# EverythingBoard.net
KiCad netlist of a schematic drawn in EasyEDA Pro
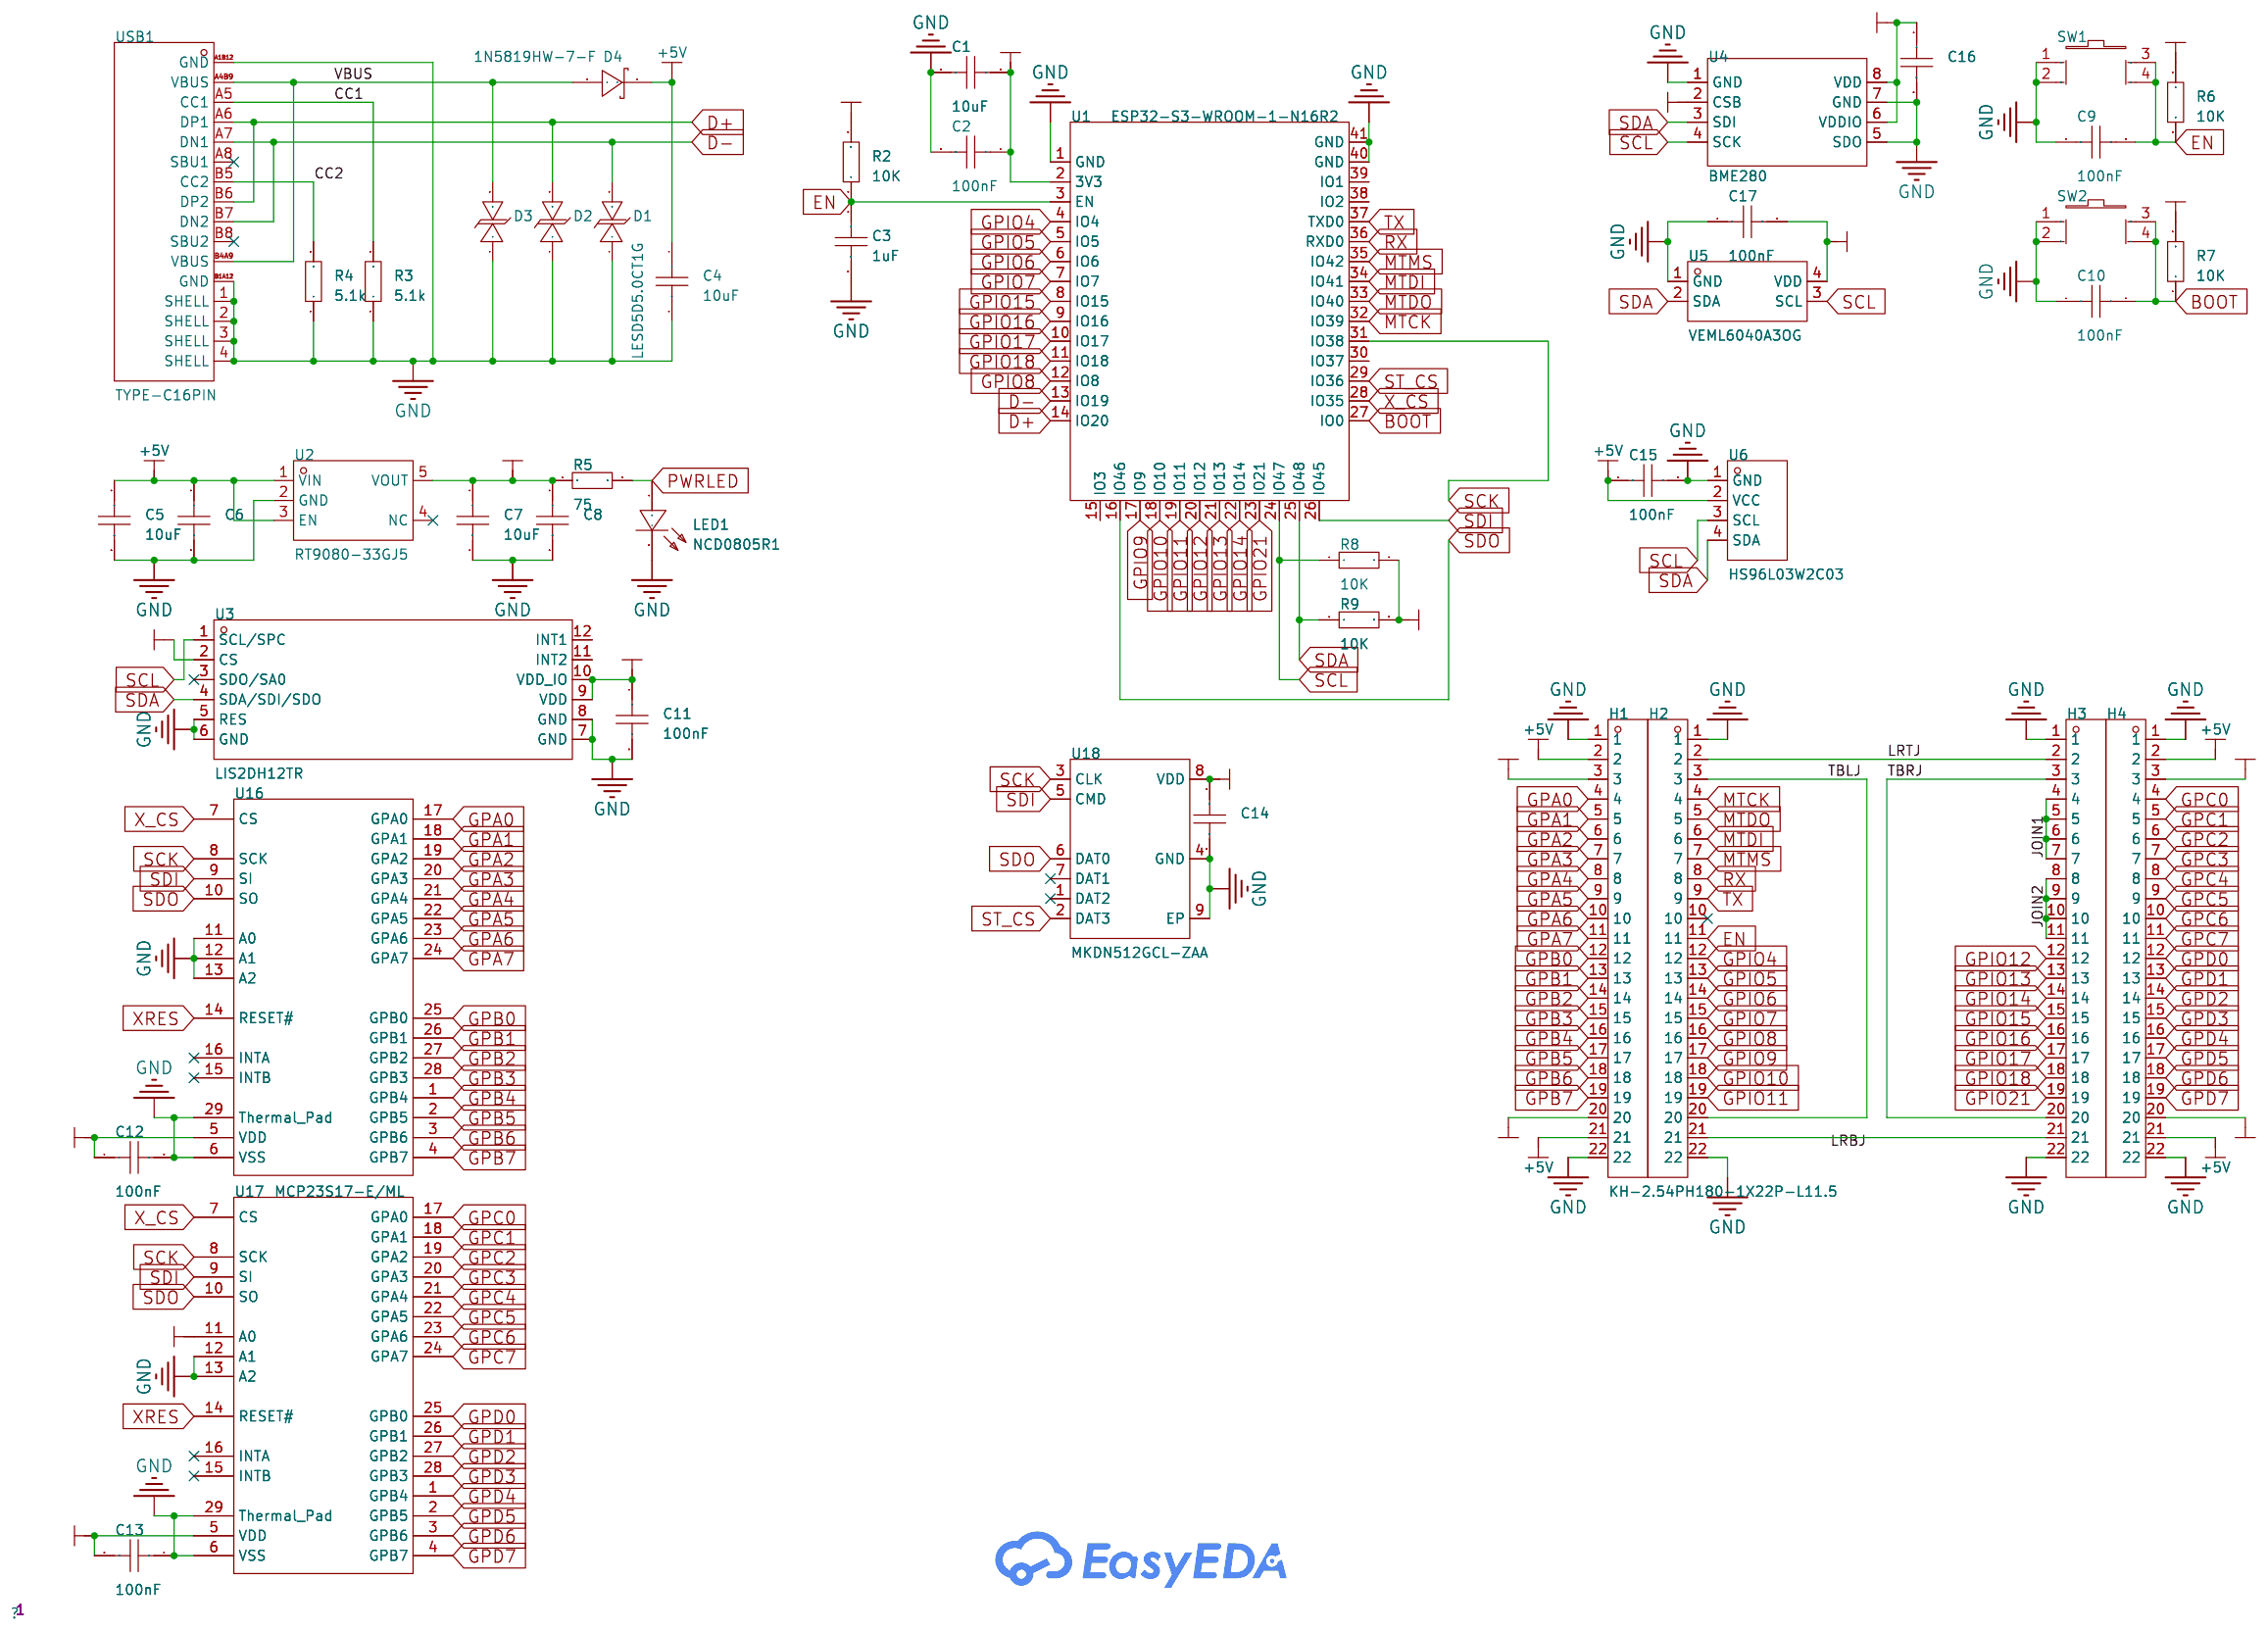
[diagram p0: schematic sheet]

(export (version "E")
  (design (tool "Eeschema 10.0.6"))
  (components
    (comp (ref "C1")
      (value "10uF")
      (footprint "easyedapro:C0603")
      (libsource (lib "easyedapro") (part "CAP"))
    )
    (comp (ref "C2")
      (value "100nF")
      (footprint "easyedapro:C0603")
      (libsource (lib "easyedapro") (part "CAP"))
    )
    (comp (ref "C3") (value "1uF") (footprint "easyedapro:C0603") (libsource (lib "easyedapro") (part "CAP")))
    (comp (ref "C4")
      (value "10uF")
      (footprint "easyedapro:C0603")
      (libsource (lib "easyedapro") (part "CAP"))
    )
    (comp (ref "C5")
      (value "10uF")
      (footprint "easyedapro:C0603")
      (libsource (lib "easyedapro") (part "CAP"))
    )
    (comp (ref "C6")
      (value "100nF")
      (footprint "easyedapro:C0603")
      (libsource (lib "easyedapro") (part "CAP"))
    )
    (comp (ref "C7")
      (value "10uF")
      (footprint "easyedapro:C0603")
      (libsource (lib "easyedapro") (part "CAP"))
    )
    (comp (ref "C8")
      (value "100nF")
      (footprint "easyedapro:C0603")
      (libsource (lib "easyedapro") (part "CAP"))
    )
    (comp (ref "C9")
      (value "100nF")
      (footprint "easyedapro:C0603")
      (libsource (lib "easyedapro") (part "CAP"))
    )
    (comp (ref "C10")
      (value "100nF")
      (footprint "easyedapro:C0603")
      (libsource (lib "easyedapro") (part "CAP"))
    )
    (comp (ref "C11")
      (value "100nF")
      (footprint "easyedapro:C0603")
      (libsource (lib "easyedapro") (part "CAP"))
    )
    (comp (ref "C12")
      (value "100nF")
      (footprint "easyedapro:C0603")
      (libsource (lib "easyedapro") (part "CAP"))
    )
    (comp (ref "C13")
      (value "100nF")
      (footprint "easyedapro:C0603")
      (libsource (lib "easyedapro") (part "CAP"))
    )
    (comp (ref "C14")
      (value "100nF")
      (footprint "easyedapro:C0603")
      (libsource (lib "easyedapro") (part "CAP"))
    )
    (comp (ref "C15")
      (value "100nF")
      (footprint "easyedapro:C0603")
      (libsource (lib "easyedapro") (part "CAP"))
    )
    (comp (ref "C16")
      (value "100nF")
      (footprint "easyedapro:C0603")
      (libsource (lib "easyedapro") (part "CAP"))
    )
    (comp (ref "C17")
      (value "100nF")
      (footprint "easyedapro:C0603")
      (libsource (lib "easyedapro") (part "CAP"))
    )
    (comp (ref "D1")
      (value "LESD5D5.0CT1G")
      (footprint "easyedapro:SOD-523_L1.2-W0.8-LS1.6-BI")
      (fields (field (name "Manufacturer") "UMW(友台半导体)"))
      (libsource (lib "easyedapro") (part "LESD5D5.0CT1G_C5199850"))
    )
    (comp (ref "D2")
      (value "LESD5D5.0CT1G")
      (footprint "easyedapro:SOD-523_L1.2-W0.8-LS1.6-BI")
      (fields (field (name "Manufacturer") "UMW(友台半导体)"))
      (libsource (lib "easyedapro") (part "LESD5D5.0CT1G_C5199850"))
    )
    (comp (ref "D3")
      (value "LESD5D5.0CT1G")
      (footprint "easyedapro:SOD-523_L1.2-W0.8-LS1.6-BI")
      (fields (field (name "Manufacturer") "UMW(友台半导体)"))
      (libsource (lib "easyedapro") (part "LESD5D5.0CT1G_C5199850"))
    )
    (comp (ref "D4")
      (value "1N5819HW-7-F")
      (footprint "easyedapro:SOD-123_L2.7-W1.6-LS3.7-RD")
      (fields (field (name "Manufacturer") "DIODES(美台)"))
      (libsource (lib "easyedapro") (part "1N5819HW-7-F"))
    )
    (comp (ref "H1")
      (value "KH-2.54PH180-1X22P-L11.5")
      (footprint "easyedapro:HDR-TH_22P-P2.54-V-M")
      (description "Pin Structure:1x22P Pitch:2.54mm Number of Rows:Single Row")
      (fields (field (name "Manufacturer") "kinghelm(金航标)"))
      (libsource (lib "easyedapro") (part "KH-2.54PH180-1X22P-L11.5"))
    )
    (comp (ref "H2")
      (value "KH-2.54PH180-1X22P-L11.5")
      (footprint "easyedapro:HDR-TH_22P-P2.54-V-M")
      (description "Pin Structure:1x22P Pitch:2.54mm Number of Rows:Single Row")
      (fields (field (name "Manufacturer") "kinghelm(金航标)"))
      (libsource (lib "easyedapro") (part "KH-2.54PH180-1X22P-L11.5"))
    )
    (comp (ref "H3")
      (value "KH-2.54PH180-1X22P-L11.5")
      (footprint "easyedapro:HDR-TH_22P-P2.54-V-M")
      (description "Pin Structure:1x22P Pitch:2.54mm Number of Rows:Single Row")
      (fields (field (name "Manufacturer") "kinghelm(金航标)"))
      (libsource (lib "easyedapro") (part "KH-2.54PH180-1X22P-L11.5"))
    )
    (comp (ref "H4")
      (value "KH-2.54PH180-1X22P-L11.5")
      (footprint "easyedapro:HDR-TH_22P-P2.54-V-M")
      (description "Pin Structure:1x22P Pitch:2.54mm Number of Rows:Single Row")
      (fields (field (name "Manufacturer") "kinghelm(金航标)"))
      (libsource (lib "easyedapro") (part "KH-2.54PH180-1X22P-L11.5"))
    )
    (comp (ref "LED1")
      (value "NCD0805R1")
      (footprint "easyedapro:LED0805-R-RD")
      (fields (field (name "Manufacturer") "国星光电"))
      (libsource (lib "easyedapro") (part "FC-2012HRK-620D"))
    )
    (comp (ref "R2") (value "10K") (footprint "easyedapro:R0603") (libsource (lib "easyedapro") (part "Res")))
    (comp (ref "R3")
      (value "5.1k")
      (footprint "easyedapro:R0603")
      (libsource (lib "easyedapro") (part "Res"))
    )
    (comp (ref "R4")
      (value "5.1k")
      (footprint "easyedapro:R0603")
      (libsource (lib "easyedapro") (part "Res"))
    )
    (comp (ref "R5") (value "75") (footprint "easyedapro:R0603") (libsource (lib "easyedapro") (part "Res")))
    (comp (ref "R6") (value "10K") (footprint "easyedapro:R0603") (libsource (lib "easyedapro") (part "Res")))
    (comp (ref "R7") (value "10K") (footprint "easyedapro:R0603") (libsource (lib "easyedapro") (part "Res")))
    (comp (ref "R8") (value "10K") (footprint "easyedapro:R0603") (libsource (lib "easyedapro") (part "Res")))
    (comp (ref "R9") (value "10K") (footprint "easyedapro:R0603") (libsource (lib "easyedapro") (part "Res")))
    (comp (ref "SW1")
      (value "PTS810SJG250SMTRLFS")
      (footprint "easyedapro:SW-SMD_4P_PTS810SJM250SMTRLFS")
      (fields (field (name "Manufacturer") "C&K"))
      (libsource (lib "easyedapro") (part "PTS810SJG250SMTRLFS"))
    )
    (comp (ref "SW2")
      (value "PTS810SJG250SMTRLFS")
      (footprint "easyedapro:SW-SMD_4P_PTS810SJM250SMTRLFS")
      (fields (field (name "Manufacturer") "C&K"))
      (libsource (lib "easyedapro") (part "PTS810SJG250SMTRLFS"))
    )
    (comp (ref "U1")
      (value "ESP32-S3-WROOM-1-N16R2")
      (footprint "easyedapro:WIRELM-SMD_ESP32-S3-WROOM-1")
      (fields (field (name "Manufacturer") "ESPRESSIF(乐鑫)"))
      (libsource (lib "easyedapro") (part "ESP32-S3-WROOM-1(N16R2)"))
    )
    (comp (ref "U2")
      (value "RT9080-33GJ5")
      (footprint "easyedapro:TSOT-23-5_L2.9-W1.6-P0.95-LS2.8-BL")
      (description "+3V3")
      (fields (field (name "Manufacturer") "RICHTEK(立锜)"))
      (libsource (lib "easyedapro") (part "RT9080-33GJ5"))
    )
    (comp (ref "U3")
      (value "LIS2DH12TR")
      (footprint "easyedapro:LGA-12_L2.0-W2.0-P0.50-BL")
      (fields (field (name "Manufacturer") "ST(意法半导体)"))
      (libsource (lib "easyedapro") (part "LIS2DH12TR"))
    )
    (comp (ref "U4")
      (value "BME280")
      (footprint "easyedapro:LGA-8_BME280_BL")
      (description "Voltage - Supply:1.71V~3.6V Voltage - Supply:1.71V~3.6V")
      (fields (field (name "Manufacturer") "Bosch(博世)"))
      (libsource (lib "easyedapro") (part "BME280"))
    )
    (comp (ref "U5")
      (value "VEML6040A3OG")
      (footprint "easyedapro:SENSOR_SMD_VEML6040A3OG")
      (fields (field (name "Manufacturer") "VISHAY(威世)"))
      (libsource (lib "easyedapro") (part "VEML6040A3OG"))
    )
    (comp (ref "U6")
      (value "HS96L03W2C03")
      (footprint "easyedapro:OLED-TH_L27.8-W27.2-P2.54_C9900033791")
      (fields (field (name "Manufacturer") "HS(汉昇)"))
      (libsource (lib "easyedapro") (part "HS96L03W2C03"))
    )
    (comp (ref "U16")
      (value "MCP23S17-E/ML")
      (footprint "easyedapro:QFN-28_L6.0-W6.0-P0.65-BL-EP")
      (fields (field (name "Manufacturer") "MICROCHIP(美国微芯)"))
      (libsource (lib "easyedapro") (part "MCP23S17-E/ML"))
    )
    (comp (ref "U17")
      (value "MCP23S17-E/ML")
      (footprint "easyedapro:QFN-28_L6.0-W6.0-P0.65-BL-EP")
      (fields (field (name "Manufacturer") "MICROCHIP(美国微芯)"))
      (libsource (lib "easyedapro") (part "MCP23S17-E/ML"))
    )
    (comp (ref "U18")
      (value "MKDN512GCL-ZAA")
      (footprint "easyedapro:LGA-16_L12.5-W9.0-P1.27-TL-EP")
      (fields (field (name "Manufacturer") "MK(米客方德)"))
      (libsource (lib "easyedapro") (part "MKDN512GCL-ZAA"))
    )
    (comp (ref "USB1")
      (value "TYPE-C16PIN")
      (footprint "easyedapro:USB-C-SMD_TYPE-C16PIN")
      (fields (field (name "Manufacturer") "SHOU HAN(首韩)"))
      (libsource (lib "easyedapro") (part "TYPE-C16PIN"))
    )
  )
  (nets
    (net (code "1") (name "+3V3") (class "Default")
      (node (ref "C1") (pin "1") (pinfunction "1_1") (pintype "input"))
      (node (ref "C11") (pin "1") (pinfunction "1_1") (pintype "input"))
      (node (ref "C12") (pin "1") (pinfunction "1_1") (pintype "input"))
      (node (ref "C13") (pin "2") (pinfunction "2_2") (pintype "input"))
      (node (ref "C14") (pin "1") (pinfunction "1_1") (pintype "input"))
      (node (ref "C16") (pin "1") (pinfunction "1_1") (pintype "input"))
      (node (ref "C17") (pin "2") (pinfunction "2_2") (pintype "input"))
      (node (ref "C2") (pin "1") (pinfunction "1_1") (pintype "input"))
      (node (ref "C7") (pin "1") (pinfunction "1_1") (pintype "input"))
      (node (ref "C8") (pin "1") (pinfunction "1_1") (pintype "input"))
      (node (ref "H1") (pin "20") (pinfunction "20_20") (pintype "unspecified"))
      (node (ref "H1") (pin "3") (pinfunction "3_3") (pintype "unspecified"))
      (node (ref "H4") (pin "20") (pinfunction "20_20") (pintype "unspecified"))
      (node (ref "H4") (pin "3") (pinfunction "3_3") (pintype "unspecified"))
      (node (ref "R2") (pin "2") (pinfunction "2_2") (pintype "input"))
      (node (ref "R5") (pin "1") (pinfunction "1_1") (pintype "input"))
      (node (ref "R6") (pin "1") (pinfunction "1_1") (pintype "input"))
      (node (ref "R7") (pin "2") (pinfunction "2_2") (pintype "input"))
      (node (ref "R8") (pin "2") (pinfunction "2_2") (pintype "input"))
      (node (ref "R9") (pin "2") (pinfunction "2_2") (pintype "input"))
      (node (ref "U1") (pin "2") (pinfunction "3V3_2") (pintype "unspecified"))
      (node (ref "U16") (pin "5") (pinfunction "VDD_5") (pintype "input"))
      (node (ref "U17") (pin "11") (pinfunction "A0_11") (pintype "input"))
      (node (ref "U17") (pin "5") (pinfunction "VDD_5") (pintype "input"))
      (node (ref "U18") (pin "8") (pinfunction "VDD_8") (pintype "unspecified"))
      (node (ref "U2") (pin "5") (pinfunction "VOUT_5") (pintype "unspecified"))
      (node (ref "U3") (pin "10") (pinfunction "VDD_IO_10") (pintype "unspecified"))
      (node (ref "U3") (pin "2") (pinfunction "CS_2") (pintype "unspecified"))
      (node (ref "U3") (pin "9") (pinfunction "VDD_9") (pintype "unspecified"))
      (node (ref "U4") (pin "2") (pinfunction "CSB_2") (pintype "unspecified"))
      (node (ref "U4") (pin "6") (pinfunction "VDDIO_6") (pintype "unspecified"))
      (node (ref "U4") (pin "8") (pinfunction "VDD_8") (pintype "unspecified"))
      (node (ref "U5") (pin "4") (pinfunction "VDD_4") (pintype "unspecified"))
    )
    (net (code "2") (name "+5V") (class "Default")
      (node (ref "C15") (pin "1") (pinfunction "1_1") (pintype "input"))
      (node (ref "C4") (pin "1") (pinfunction "1_1") (pintype "input"))
      (node (ref "C5") (pin "1") (pinfunction "1_1") (pintype "input"))
      (node (ref "C6") (pin "1") (pinfunction "1_1") (pintype "input"))
      (node (ref "D4") (pin "1") (pinfunction "K_1") (pintype "unspecified"))
      (node (ref "H1") (pin "2") (pinfunction "2_2") (pintype "unspecified"))
      (node (ref "H1") (pin "21") (pinfunction "21_21") (pintype "unspecified"))
      (node (ref "H4") (pin "2") (pinfunction "2_2") (pintype "unspecified"))
      (node (ref "H4") (pin "21") (pinfunction "21_21") (pintype "unspecified"))
      (node (ref "U2") (pin "1") (pinfunction "VIN_1") (pintype "unspecified"))
      (node (ref "U2") (pin "3") (pinfunction "EN_3") (pintype "unspecified"))
      (node (ref "U6") (pin "2") (pinfunction "VCC_2") (pintype "unspecified"))
    )
    (net (code "3") (name "/CC1") (class "Default")
      (node (ref "R3") (pin "2") (pinfunction "2_2") (pintype "input"))
      (node (ref "USB1") (pin "A5") (pinfunction "CC1_A5") (pintype "unspecified"))
    )
    (net (code "4") (name "/CC2") (class "Default")
      (node (ref "R4") (pin "2") (pinfunction "2_2") (pintype "input"))
      (node (ref "USB1") (pin "B5") (pinfunction "CC2_B5") (pintype "unspecified"))
    )
    (net (code "5") (name "/JOIN1") (class "Default")
      (node (ref "H3") (pin "4") (pinfunction "4_4") (pintype "unspecified"))
      (node (ref "H3") (pin "5") (pinfunction "5_5") (pintype "unspecified"))
      (node (ref "H3") (pin "6") (pinfunction "6_6") (pintype "unspecified"))
      (node (ref "H3") (pin "7") (pinfunction "7_7") (pintype "unspecified"))
    )
    (net (code "6") (name "/JOIN2") (class "Default")
      (node (ref "H3") (pin "10") (pinfunction "10_10") (pintype "unspecified"))
      (node (ref "H3") (pin "11") (pinfunction "11_11") (pintype "unspecified"))
      (node (ref "H3") (pin "8") (pinfunction "8_8") (pintype "unspecified"))
      (node (ref "H3") (pin "9") (pinfunction "9_9") (pintype "unspecified"))
    )
    (net (code "7") (name "/LRBJ") (class "Default")
      (node (ref "H2") (pin "21") (pinfunction "21_21") (pintype "unspecified"))
      (node (ref "H3") (pin "21") (pinfunction "21_21") (pintype "unspecified"))
    )
    (net (code "8") (name "/LRTJ") (class "Default")
      (node (ref "H2") (pin "2") (pinfunction "2_2") (pintype "unspecified"))
      (node (ref "H3") (pin "2") (pinfunction "2_2") (pintype "unspecified"))
    )
    (net (code "9") (name "/TBLJ") (class "Default")
      (node (ref "H2") (pin "20") (pinfunction "20_20") (pintype "unspecified"))
      (node (ref "H2") (pin "3") (pinfunction "3_3") (pintype "unspecified"))
    )
    (net (code "10") (name "/TBRJ") (class "Default")
      (node (ref "H3") (pin "20") (pinfunction "20_20") (pintype "unspecified"))
      (node (ref "H3") (pin "3") (pinfunction "3_3") (pintype "unspecified"))
    )
    (net (code "11") (name "/VBUS") (class "Default")
      (node (ref "D3") (pin "2") (pinfunction "2_2") (pintype "unspecified"))
      (node (ref "D4") (pin "2") (pinfunction "A_2") (pintype "unspecified"))
      (node (ref "USB1") (pin "A4B9") (pinfunction "VBUS_A4B9") (pintype "unspecified"))
      (node (ref "USB1") (pin "B4A9") (pinfunction "VBUS_B4A9") (pintype "unspecified"))
    )
    (net (code "12") (name "BOOT") (class "Default")
      (node (ref "C10") (pin "2") (pinfunction "2_2") (pintype "input"))
      (node (ref "R7") (pin "1") (pinfunction "1_1") (pintype "input"))
      (node (ref "SW2") (pin "3") (pinfunction "3_3") (pintype "input"))
      (node (ref "SW2") (pin "4") (pinfunction "4_4") (pintype "input"))
      (node (ref "U1") (pin "27") (pinfunction "IO0_27") (pintype "unspecified"))
    )
    (net (code "13") (name "D+") (class "Default")
      (node (ref "D2") (pin "2") (pinfunction "2_2") (pintype "unspecified"))
      (node (ref "U1") (pin "14") (pinfunction "IO20_14") (pintype "unspecified"))
      (node (ref "USB1") (pin "A6") (pinfunction "DP1_A6") (pintype "unspecified"))
      (node (ref "USB1") (pin "B6") (pinfunction "DP2_B6") (pintype "unspecified"))
    )
    (net (code "14") (name "D-") (class "Default")
      (node (ref "D1") (pin "2") (pinfunction "2_2") (pintype "unspecified"))
      (node (ref "U1") (pin "13") (pinfunction "IO19_13") (pintype "unspecified"))
      (node (ref "USB1") (pin "A7") (pinfunction "DN1_A7") (pintype "unspecified"))
      (node (ref "USB1") (pin "B7") (pinfunction "DN2_B7") (pintype "unspecified"))
    )
    (net (code "15") (name "EN") (class "Default")
      (node (ref "C3") (pin "1") (pinfunction "1_1") (pintype "input"))
      (node (ref "C9") (pin "2") (pinfunction "2_2") (pintype "input"))
      (node (ref "H2") (pin "11") (pinfunction "11_11") (pintype "unspecified"))
      (node (ref "R2") (pin "1") (pinfunction "1_1") (pintype "input"))
      (node (ref "R6") (pin "2") (pinfunction "2_2") (pintype "input"))
      (node (ref "SW1") (pin "3") (pinfunction "3_3") (pintype "input"))
      (node (ref "SW1") (pin "4") (pinfunction "4_4") (pintype "input"))
      (node (ref "U1") (pin "3") (pinfunction "EN_3") (pintype "unspecified"))
    )
    (net (code "16") (name "GND") (class "Default")
      (node (ref "C1") (pin "2") (pinfunction "2_2") (pintype "input"))
      (node (ref "C10") (pin "1") (pinfunction "1_1") (pintype "input"))
      (node (ref "C11") (pin "2") (pinfunction "2_2") (pintype "input"))
      (node (ref "C12") (pin "2") (pinfunction "2_2") (pintype "input"))
      (node (ref "C13") (pin "1") (pinfunction "1_1") (pintype "input"))
      (node (ref "C14") (pin "2") (pinfunction "2_2") (pintype "input"))
      (node (ref "C15") (pin "2") (pinfunction "2_2") (pintype "input"))
      (node (ref "C16") (pin "2") (pinfunction "2_2") (pintype "input"))
      (node (ref "C17") (pin "1") (pinfunction "1_1") (pintype "input"))
      (node (ref "C2") (pin "2") (pinfunction "2_2") (pintype "input"))
      (node (ref "C3") (pin "2") (pinfunction "2_2") (pintype "input"))
      (node (ref "C4") (pin "2") (pinfunction "2_2") (pintype "input"))
      (node (ref "C5") (pin "2") (pinfunction "2_2") (pintype "input"))
      (node (ref "C6") (pin "2") (pinfunction "2_2") (pintype "input"))
      (node (ref "C7") (pin "2") (pinfunction "2_2") (pintype "input"))
      (node (ref "C8") (pin "2") (pinfunction "2_2") (pintype "input"))
      (node (ref "C9") (pin "1") (pinfunction "1_1") (pintype "input"))
      (node (ref "D1") (pin "1") (pinfunction "1_1") (pintype "unspecified"))
      (node (ref "D2") (pin "1") (pinfunction "1_1") (pintype "unspecified"))
      (node (ref "D3") (pin "1") (pinfunction "1_1") (pintype "unspecified"))
      (node (ref "H1") (pin "1") (pinfunction "1_1") (pintype "unspecified"))
      (node (ref "H1") (pin "22") (pinfunction "22_22") (pintype "unspecified"))
      (node (ref "H2") (pin "1") (pinfunction "1_1") (pintype "unspecified"))
      (node (ref "H2") (pin "22") (pinfunction "22_22") (pintype "unspecified"))
      (node (ref "H3") (pin "1") (pinfunction "1_1") (pintype "unspecified"))
      (node (ref "H3") (pin "22") (pinfunction "22_22") (pintype "unspecified"))
      (node (ref "H4") (pin "1") (pinfunction "1_1") (pintype "unspecified"))
      (node (ref "H4") (pin "22") (pinfunction "22_22") (pintype "unspecified"))
      (node (ref "LED1") (pin "2") (pinfunction "-_2") (pintype "unspecified"))
      (node (ref "R3") (pin "1") (pinfunction "1_1") (pintype "input"))
      (node (ref "R4") (pin "1") (pinfunction "1_1") (pintype "input"))
      (node (ref "SW1") (pin "1") (pinfunction "1_1") (pintype "input"))
      (node (ref "SW1") (pin "2") (pinfunction "2_2") (pintype "input"))
      (node (ref "SW2") (pin "1") (pinfunction "1_1") (pintype "input"))
      (node (ref "SW2") (pin "2") (pinfunction "2_2") (pintype "input"))
      (node (ref "U1") (pin "1") (pinfunction "GND_1") (pintype "unspecified"))
      (node (ref "U1") (pin "40") (pinfunction "GND_40") (pintype "unspecified"))
      (node (ref "U1") (pin "41") (pinfunction "GND_41") (pintype "unspecified"))
      (node (ref "U16") (pin "11") (pinfunction "A0_11") (pintype "input"))
      (node (ref "U16") (pin "12") (pinfunction "A1_12") (pintype "input"))
      (node (ref "U16") (pin "13") (pinfunction "A2_13") (pintype "input"))
      (node (ref "U16") (pin "29") (pinfunction "Thermal_Pad_29") (pintype "input"))
      (node (ref "U16") (pin "6") (pinfunction "VSS_6") (pintype "input"))
      (node (ref "U17") (pin "12") (pinfunction "A1_12") (pintype "input"))
      (node (ref "U17") (pin "13") (pinfunction "A2_13") (pintype "input"))
      (node (ref "U17") (pin "29") (pinfunction "Thermal_Pad_29") (pintype "input"))
      (node (ref "U17") (pin "6") (pinfunction "VSS_6") (pintype "input"))
      (node (ref "U18") (pin "4") (pinfunction "GND_4") (pintype "unspecified"))
      (node (ref "U18") (pin "9") (pinfunction "EP_9") (pintype "unspecified"))
      (node (ref "U2") (pin "2") (pinfunction "GND_2") (pintype "unspecified"))
      (node (ref "U3") (pin "5") (pinfunction "RES_5") (pintype "unspecified"))
      (node (ref "U3") (pin "6") (pinfunction "GND_6") (pintype "unspecified"))
      (node (ref "U3") (pin "7") (pinfunction "GND_7") (pintype "unspecified"))
      (node (ref "U3") (pin "8") (pinfunction "GND_8") (pintype "unspecified"))
      (node (ref "U4") (pin "1") (pinfunction "GND_1") (pintype "unspecified"))
      (node (ref "U4") (pin "5") (pinfunction "SDO_5") (pintype "unspecified"))
      (node (ref "U4") (pin "7") (pinfunction "GND_7") (pintype "unspecified"))
      (node (ref "U5") (pin "1") (pinfunction "GND_1") (pintype "unspecified"))
      (node (ref "U6") (pin "1") (pinfunction "GND_1") (pintype "unspecified"))
      (node (ref "USB1") (pin "1") (pinfunction "SHELL_1") (pintype "unspecified"))
      (node (ref "USB1") (pin "2") (pinfunction "SHELL_2") (pintype "unspecified"))
      (node (ref "USB1") (pin "3") (pinfunction "SHELL_3") (pintype "unspecified"))
      (node (ref "USB1") (pin "4") (pinfunction "SHELL_4") (pintype "unspecified"))
      (node (ref "USB1") (pin "A1B12") (pinfunction "GND_A1B12") (pintype "unspecified"))
      (node (ref "USB1") (pin "B1A12") (pinfunction "GND_B1A12") (pintype "unspecified"))
    )
    (net (code "17") (name "GPA0") (class "Default")
      (node (ref "H1") (pin "4") (pinfunction "4_4") (pintype "unspecified"))
      (node (ref "U16") (pin "17") (pinfunction "GPA0_17") (pintype "bidirectional"))
    )
    (net (code "18") (name "GPA1") (class "Default")
      (node (ref "H1") (pin "5") (pinfunction "5_5") (pintype "unspecified"))
      (node (ref "U16") (pin "18") (pinfunction "GPA1_18") (pintype "bidirectional"))
    )
    (net (code "19") (name "GPA2") (class "Default")
      (node (ref "H1") (pin "6") (pinfunction "6_6") (pintype "unspecified"))
      (node (ref "U16") (pin "19") (pinfunction "GPA2_19") (pintype "bidirectional"))
    )
    (net (code "20") (name "GPA3") (class "Default")
      (node (ref "H1") (pin "7") (pinfunction "7_7") (pintype "unspecified"))
      (node (ref "U16") (pin "20") (pinfunction "GPA3_20") (pintype "bidirectional"))
    )
    (net (code "21") (name "GPA4") (class "Default")
      (node (ref "H1") (pin "8") (pinfunction "8_8") (pintype "unspecified"))
      (node (ref "U16") (pin "21") (pinfunction "GPA4_21") (pintype "bidirectional"))
    )
    (net (code "22") (name "GPA5") (class "Default")
      (node (ref "H1") (pin "9") (pinfunction "9_9") (pintype "unspecified"))
      (node (ref "U16") (pin "22") (pinfunction "GPA5_22") (pintype "bidirectional"))
    )
    (net (code "23") (name "GPA6") (class "Default")
      (node (ref "H1") (pin "10") (pinfunction "10_10") (pintype "unspecified"))
      (node (ref "U16") (pin "23") (pinfunction "GPA6_23") (pintype "bidirectional"))
    )
    (net (code "24") (name "GPA7") (class "Default")
      (node (ref "H1") (pin "11") (pinfunction "11_11") (pintype "unspecified"))
      (node (ref "U16") (pin "24") (pinfunction "GPA7_24") (pintype "bidirectional"))
    )
    (net (code "25") (name "GPB0") (class "Default")
      (node (ref "H1") (pin "12") (pinfunction "12_12") (pintype "unspecified"))
      (node (ref "U16") (pin "25") (pinfunction "GPB0_25") (pintype "bidirectional"))
    )
    (net (code "26") (name "GPB1") (class "Default")
      (node (ref "H1") (pin "13") (pinfunction "13_13") (pintype "unspecified"))
      (node (ref "U16") (pin "26") (pinfunction "GPB1_26") (pintype "bidirectional"))
    )
    (net (code "27") (name "GPB2") (class "Default")
      (node (ref "H1") (pin "14") (pinfunction "14_14") (pintype "unspecified"))
      (node (ref "U16") (pin "27") (pinfunction "GPB2_27") (pintype "bidirectional"))
    )
    (net (code "28") (name "GPB3") (class "Default")
      (node (ref "H1") (pin "15") (pinfunction "15_15") (pintype "unspecified"))
      (node (ref "U16") (pin "28") (pinfunction "GPB3_28") (pintype "bidirectional"))
    )
    (net (code "29") (name "GPB4") (class "Default")
      (node (ref "H1") (pin "16") (pinfunction "16_16") (pintype "unspecified"))
      (node (ref "U16") (pin "1") (pinfunction "GPB4_1") (pintype "bidirectional"))
    )
    (net (code "30") (name "GPB5") (class "Default")
      (node (ref "H1") (pin "17") (pinfunction "17_17") (pintype "unspecified"))
      (node (ref "U16") (pin "2") (pinfunction "GPB5_2") (pintype "bidirectional"))
    )
    (net (code "31") (name "GPB6") (class "Default")
      (node (ref "H1") (pin "18") (pinfunction "18_18") (pintype "unspecified"))
      (node (ref "U16") (pin "3") (pinfunction "GPB6_3") (pintype "bidirectional"))
    )
    (net (code "32") (name "GPB7") (class "Default")
      (node (ref "H1") (pin "19") (pinfunction "19_19") (pintype "unspecified"))
      (node (ref "U16") (pin "4") (pinfunction "GPB7_4") (pintype "bidirectional"))
    )
    (net (code "33") (name "GPC0") (class "Default")
      (node (ref "H4") (pin "4") (pinfunction "4_4") (pintype "unspecified"))
      (node (ref "U17") (pin "17") (pinfunction "GPA0_17") (pintype "bidirectional"))
    )
    (net (code "34") (name "GPC1") (class "Default")
      (node (ref "H4") (pin "5") (pinfunction "5_5") (pintype "unspecified"))
      (node (ref "U17") (pin "18") (pinfunction "GPA1_18") (pintype "bidirectional"))
    )
    (net (code "35") (name "GPC2") (class "Default")
      (node (ref "H4") (pin "6") (pinfunction "6_6") (pintype "unspecified"))
      (node (ref "U17") (pin "19") (pinfunction "GPA2_19") (pintype "bidirectional"))
    )
    (net (code "36") (name "GPC3") (class "Default")
      (node (ref "H4") (pin "7") (pinfunction "7_7") (pintype "unspecified"))
      (node (ref "U17") (pin "20") (pinfunction "GPA3_20") (pintype "bidirectional"))
    )
    (net (code "37") (name "GPC4") (class "Default")
      (node (ref "H4") (pin "8") (pinfunction "8_8") (pintype "unspecified"))
      (node (ref "U17") (pin "21") (pinfunction "GPA4_21") (pintype "bidirectional"))
    )
    (net (code "38") (name "GPC5") (class "Default")
      (node (ref "H4") (pin "9") (pinfunction "9_9") (pintype "unspecified"))
      (node (ref "U17") (pin "22") (pinfunction "GPA5_22") (pintype "bidirectional"))
    )
    (net (code "39") (name "GPC6") (class "Default")
      (node (ref "H4") (pin "10") (pinfunction "10_10") (pintype "unspecified"))
      (node (ref "U17") (pin "23") (pinfunction "GPA6_23") (pintype "bidirectional"))
    )
    (net (code "40") (name "GPC7") (class "Default")
      (node (ref "H4") (pin "11") (pinfunction "11_11") (pintype "unspecified"))
      (node (ref "U17") (pin "24") (pinfunction "GPA7_24") (pintype "bidirectional"))
    )
    (net (code "41") (name "GPD0") (class "Default")
      (node (ref "H4") (pin "12") (pinfunction "12_12") (pintype "unspecified"))
      (node (ref "U17") (pin "25") (pinfunction "GPB0_25") (pintype "bidirectional"))
    )
    (net (code "42") (name "GPD1") (class "Default")
      (node (ref "H4") (pin "13") (pinfunction "13_13") (pintype "unspecified"))
      (node (ref "U17") (pin "26") (pinfunction "GPB1_26") (pintype "bidirectional"))
    )
    (net (code "43") (name "GPD2") (class "Default")
      (node (ref "H4") (pin "14") (pinfunction "14_14") (pintype "unspecified"))
      (node (ref "U17") (pin "27") (pinfunction "GPB2_27") (pintype "bidirectional"))
    )
    (net (code "44") (name "GPD3") (class "Default")
      (node (ref "H4") (pin "15") (pinfunction "15_15") (pintype "unspecified"))
      (node (ref "U17") (pin "28") (pinfunction "GPB3_28") (pintype "bidirectional"))
    )
    (net (code "45") (name "GPD4") (class "Default")
      (node (ref "H4") (pin "16") (pinfunction "16_16") (pintype "unspecified"))
      (node (ref "U17") (pin "1") (pinfunction "GPB4_1") (pintype "bidirectional"))
    )
    (net (code "46") (name "GPD5") (class "Default")
      (node (ref "H4") (pin "17") (pinfunction "17_17") (pintype "unspecified"))
      (node (ref "U17") (pin "2") (pinfunction "GPB5_2") (pintype "bidirectional"))
    )
    (net (code "47") (name "GPD6") (class "Default")
      (node (ref "H4") (pin "18") (pinfunction "18_18") (pintype "unspecified"))
      (node (ref "U17") (pin "3") (pinfunction "GPB6_3") (pintype "bidirectional"))
    )
    (net (code "48") (name "GPD7") (class "Default")
      (node (ref "H4") (pin "19") (pinfunction "19_19") (pintype "unspecified"))
      (node (ref "U17") (pin "4") (pinfunction "GPB7_4") (pintype "bidirectional"))
    )
    (net (code "49") (name "GPIO4") (class "Default")
      (node (ref "H2") (pin "12") (pinfunction "12_12") (pintype "unspecified"))
      (node (ref "U1") (pin "4") (pinfunction "IO4_4") (pintype "unspecified"))
    )
    (net (code "50") (name "GPIO5") (class "Default")
      (node (ref "H2") (pin "13") (pinfunction "13_13") (pintype "unspecified"))
      (node (ref "U1") (pin "5") (pinfunction "IO5_5") (pintype "unspecified"))
    )
    (net (code "51") (name "GPIO6") (class "Default")
      (node (ref "H2") (pin "14") (pinfunction "14_14") (pintype "unspecified"))
      (node (ref "U1") (pin "6") (pinfunction "IO6_6") (pintype "unspecified"))
    )
    (net (code "52") (name "GPIO7") (class "Default")
      (node (ref "H2") (pin "15") (pinfunction "15_15") (pintype "unspecified"))
      (node (ref "U1") (pin "7") (pinfunction "IO7_7") (pintype "unspecified"))
    )
    (net (code "53") (name "GPIO8") (class "Default")
      (node (ref "H2") (pin "16") (pinfunction "16_16") (pintype "unspecified"))
      (node (ref "U1") (pin "12") (pinfunction "IO8_12") (pintype "unspecified"))
    )
    (net (code "54") (name "GPIO9") (class "Default")
      (node (ref "H2") (pin "17") (pinfunction "17_17") (pintype "unspecified"))
      (node (ref "U1") (pin "17") (pinfunction "IO9_17") (pintype "unspecified"))
    )
    (net (code "55") (name "GPIO10") (class "Default")
      (node (ref "H2") (pin "18") (pinfunction "18_18") (pintype "unspecified"))
      (node (ref "U1") (pin "18") (pinfunction "IO10_18") (pintype "unspecified"))
    )
    (net (code "56") (name "GPIO11") (class "Default")
      (node (ref "H2") (pin "19") (pinfunction "19_19") (pintype "unspecified"))
      (node (ref "U1") (pin "19") (pinfunction "IO11_19") (pintype "unspecified"))
    )
    (net (code "57") (name "GPIO12") (class "Default")
      (node (ref "H3") (pin "12") (pinfunction "12_12") (pintype "unspecified"))
      (node (ref "U1") (pin "20") (pinfunction "IO12_20") (pintype "unspecified"))
    )
    (net (code "58") (name "GPIO13") (class "Default")
      (node (ref "H3") (pin "13") (pinfunction "13_13") (pintype "unspecified"))
      (node (ref "U1") (pin "21") (pinfunction "IO13_21") (pintype "unspecified"))
    )
    (net (code "59") (name "GPIO14") (class "Default")
      (node (ref "H3") (pin "14") (pinfunction "14_14") (pintype "unspecified"))
      (node (ref "U1") (pin "22") (pinfunction "IO14_22") (pintype "unspecified"))
    )
    (net (code "60") (name "GPIO15") (class "Default")
      (node (ref "H3") (pin "15") (pinfunction "15_15") (pintype "unspecified"))
      (node (ref "U1") (pin "8") (pinfunction "IO15_8") (pintype "unspecified"))
    )
    (net (code "61") (name "GPIO16") (class "Default")
      (node (ref "H3") (pin "16") (pinfunction "16_16") (pintype "unspecified"))
      (node (ref "U1") (pin "9") (pinfunction "IO16_9") (pintype "unspecified"))
    )
    (net (code "62") (name "GPIO17") (class "Default")
      (node (ref "H3") (pin "17") (pinfunction "17_17") (pintype "unspecified"))
      (node (ref "U1") (pin "10") (pinfunction "IO17_10") (pintype "unspecified"))
    )
    (net (code "63") (name "GPIO18") (class "Default")
      (node (ref "H3") (pin "18") (pinfunction "18_18") (pintype "unspecified"))
      (node (ref "U1") (pin "11") (pinfunction "IO18_11") (pintype "unspecified"))
    )
    (net (code "64") (name "GPIO21") (class "Default")
      (node (ref "H3") (pin "19") (pinfunction "19_19") (pintype "unspecified"))
      (node (ref "U1") (pin "23") (pinfunction "IO21_23") (pintype "unspecified"))
    )
    (net (code "65") (name "MTCK") (class "Default")
      (node (ref "H2") (pin "4") (pinfunction "4_4") (pintype "unspecified"))
      (node (ref "U1") (pin "32") (pinfunction "IO39_32") (pintype "unspecified"))
    )
    (net (code "66") (name "MTDI") (class "Default")
      (node (ref "H2") (pin "6") (pinfunction "6_6") (pintype "unspecified"))
      (node (ref "U1") (pin "34") (pinfunction "IO41_34") (pintype "unspecified"))
    )
    (net (code "67") (name "MTDO") (class "Default")
      (node (ref "H2") (pin "5") (pinfunction "5_5") (pintype "unspecified"))
      (node (ref "U1") (pin "33") (pinfunction "IO40_33") (pintype "unspecified"))
    )
    (net (code "68") (name "MTMS") (class "Default")
      (node (ref "H2") (pin "7") (pinfunction "7_7") (pintype "unspecified"))
      (node (ref "U1") (pin "35") (pinfunction "IO42_35") (pintype "unspecified"))
    )
    (net (code "69") (name "PWRLED") (class "Default")
      (node (ref "LED1") (pin "1") (pinfunction "+_1") (pintype "unspecified"))
      (node (ref "R5") (pin "2") (pinfunction "2_2") (pintype "input"))
    )
    (net (code "70") (name "RX") (class "Default")
      (node (ref "H2") (pin "8") (pinfunction "8_8") (pintype "unspecified"))
      (node (ref "U1") (pin "36") (pinfunction "RXD0_36") (pintype "unspecified"))
    )
    (net (code "71") (name "SCK") (class "Default")
      (node (ref "U1") (pin "31") (pinfunction "IO38_31") (pintype "unspecified"))
      (node (ref "U16") (pin "8") (pinfunction "SCK_8") (pintype "input"))
      (node (ref "U17") (pin "8") (pinfunction "SCK_8") (pintype "input"))
      (node (ref "U18") (pin "3") (pinfunction "CLK_3") (pintype "unspecified"))
    )
    (net (code "72") (name "SCL") (class "Default")
      (node (ref "R8") (pin "1") (pinfunction "1_1") (pintype "input"))
      (node (ref "U1") (pin "24") (pinfunction "IO47_24") (pintype "unspecified"))
      (node (ref "U3") (pin "1") (pinfunction "SCL/SPC_1") (pintype "unspecified"))
      (node (ref "U4") (pin "4") (pinfunction "SCK_4") (pintype "unspecified"))
      (node (ref "U5") (pin "3") (pinfunction "SCL_3") (pintype "unspecified"))
      (node (ref "U6") (pin "3") (pinfunction "SCL_3") (pintype "unspecified"))
    )
    (net (code "73") (name "SDA") (class "Default")
      (node (ref "R9") (pin "1") (pinfunction "1_1") (pintype "input"))
      (node (ref "U1") (pin "25") (pinfunction "IO48_25") (pintype "unspecified"))
      (node (ref "U3") (pin "4") (pinfunction "SDA/SDI/SDO_4") (pintype "unspecified"))
      (node (ref "U4") (pin "3") (pinfunction "SDI_3") (pintype "unspecified"))
      (node (ref "U5") (pin "2") (pinfunction "SDA_2") (pintype "unspecified"))
      (node (ref "U6") (pin "4") (pinfunction "SDA_4") (pintype "unspecified"))
    )
    (net (code "74") (name "SDI") (class "Default")
      (node (ref "U1") (pin "26") (pinfunction "IO45_26") (pintype "unspecified"))
      (node (ref "U16") (pin "9") (pinfunction "SI_9") (pintype "input"))
      (node (ref "U17") (pin "9") (pinfunction "SI_9") (pintype "input"))
      (node (ref "U18") (pin "5") (pinfunction "CMD_5") (pintype "unspecified"))
    )
    (net (code "75") (name "SDO") (class "Default")
      (node (ref "U1") (pin "16") (pinfunction "IO46_16") (pintype "unspecified"))
      (node (ref "U16") (pin "10") (pinfunction "SO_10") (pintype "input"))
      (node (ref "U17") (pin "10") (pinfunction "SO_10") (pintype "input"))
      (node (ref "U18") (pin "6") (pinfunction "DAT0_6") (pintype "unspecified"))
    )
    (net (code "76") (name "ST_CS") (class "Default")
      (node (ref "U1") (pin "29") (pinfunction "IO36_29") (pintype "unspecified"))
      (node (ref "U18") (pin "2") (pinfunction "DAT3_2") (pintype "unspecified"))
    )
    (net (code "77") (name "TX") (class "Default")
      (node (ref "H2") (pin "9") (pinfunction "9_9") (pintype "unspecified"))
      (node (ref "U1") (pin "37") (pinfunction "TXD0_37") (pintype "unspecified"))
    )
    (net (code "78") (name "XRES") (class "Default")
      (node (ref "U16") (pin "14") (pinfunction "RESET#_14") (pintype "input"))
      (node (ref "U17") (pin "14") (pinfunction "RESET#_14") (pintype "input"))
    )
    (net (code "79") (name "X_CS") (class "Default")
      (node (ref "U1") (pin "28") (pinfunction "IO35_28") (pintype "unspecified"))
      (node (ref "U16") (pin "7") (pinfunction "CS_7") (pintype "input"))
      (node (ref "U17") (pin "7") (pinfunction "CS_7") (pintype "input"))
    )
    (net (code "80") (name "unconnected-(H2-Pad10)") (class "Default")
      (node (ref "H2") (pin "10") (pinfunction "10_10") (pintype "unspecified+no_connect"))
    )
    (net (code "81") (name "unconnected-(U1-IO1-Pad39)") (class "Default")
      (node (ref "U1") (pin "39") (pinfunction "IO1_39") (pintype "unspecified"))
    )
    (net (code "82") (name "unconnected-(U1-IO2-Pad38)") (class "Default")
      (node (ref "U1") (pin "38") (pinfunction "IO2_38") (pintype "unspecified"))
    )
    (net (code "83") (name "unconnected-(U1-IO3-Pad15)") (class "Default")
      (node (ref "U1") (pin "15") (pinfunction "IO3_15") (pintype "unspecified"))
    )
    (net (code "84") (name "unconnected-(U1-IO37-Pad30)") (class "Default")
      (node (ref "U1") (pin "30") (pinfunction "IO37_30") (pintype "unspecified"))
    )
    (net (code "85") (name "unconnected-(U2-NC-Pad4)") (class "Default")
      (node (ref "U2") (pin "4") (pinfunction "NC_4") (pintype "unspecified+no_connect"))
    )
    (net (code "86") (name "unconnected-(U3-INT1-Pad12)") (class "Default")
      (node (ref "U3") (pin "12") (pinfunction "INT1_12") (pintype "unspecified"))
    )
    (net (code "87") (name "unconnected-(U3-INT2-Pad11)") (class "Default")
      (node (ref "U3") (pin "11") (pinfunction "INT2_11") (pintype "unspecified"))
    )
    (net (code "88") (name "unconnected-(U3-SDO{slash}SA0-Pad3)") (class "Default")
      (node (ref "U3") (pin "3") (pinfunction "SDO/SA0_3") (pintype "unspecified+no_connect"))
    )
    (net (code "89") (name "unconnected-(U16-INTA-Pad16)") (class "Default")
      (node (ref "U16") (pin "16") (pinfunction "INTA_16") (pintype "input+no_connect"))
    )
    (net (code "90") (name "unconnected-(U16-INTB-Pad15)") (class "Default")
      (node (ref "U16") (pin "15") (pinfunction "INTB_15") (pintype "input+no_connect"))
    )
    (net (code "91") (name "unconnected-(U17-INTA-Pad16)") (class "Default")
      (node (ref "U17") (pin "16") (pinfunction "INTA_16") (pintype "input+no_connect"))
    )
    (net (code "92") (name "unconnected-(U17-INTB-Pad15)") (class "Default")
      (node (ref "U17") (pin "15") (pinfunction "INTB_15") (pintype "input+no_connect"))
    )
    (net (code "93") (name "unconnected-(U18-DAT1-Pad7)") (class "Default")
      (node (ref "U18") (pin "7") (pinfunction "DAT1_7") (pintype "unspecified+no_connect"))
    )
    (net (code "94") (name "unconnected-(U18-DAT2-Pad1)") (class "Default")
      (node (ref "U18") (pin "1") (pinfunction "DAT2_1") (pintype "unspecified+no_connect"))
    )
    (net (code "95") (name "unconnected-(USB1-SBU1-PadA8)") (class "Default")
      (node (ref "USB1") (pin "A8") (pinfunction "SBU1_A8") (pintype "unspecified+no_connect"))
    )
    (net (code "96") (name "unconnected-(USB1-SBU2-PadB8)") (class "Default")
      (node (ref "USB1") (pin "B8") (pinfunction "SBU2_B8") (pintype "unspecified+no_connect"))
    )
  )
)
